# SensorsConnectorBrd.net
KiCad netlist of a schematic drawn in Altium Designer
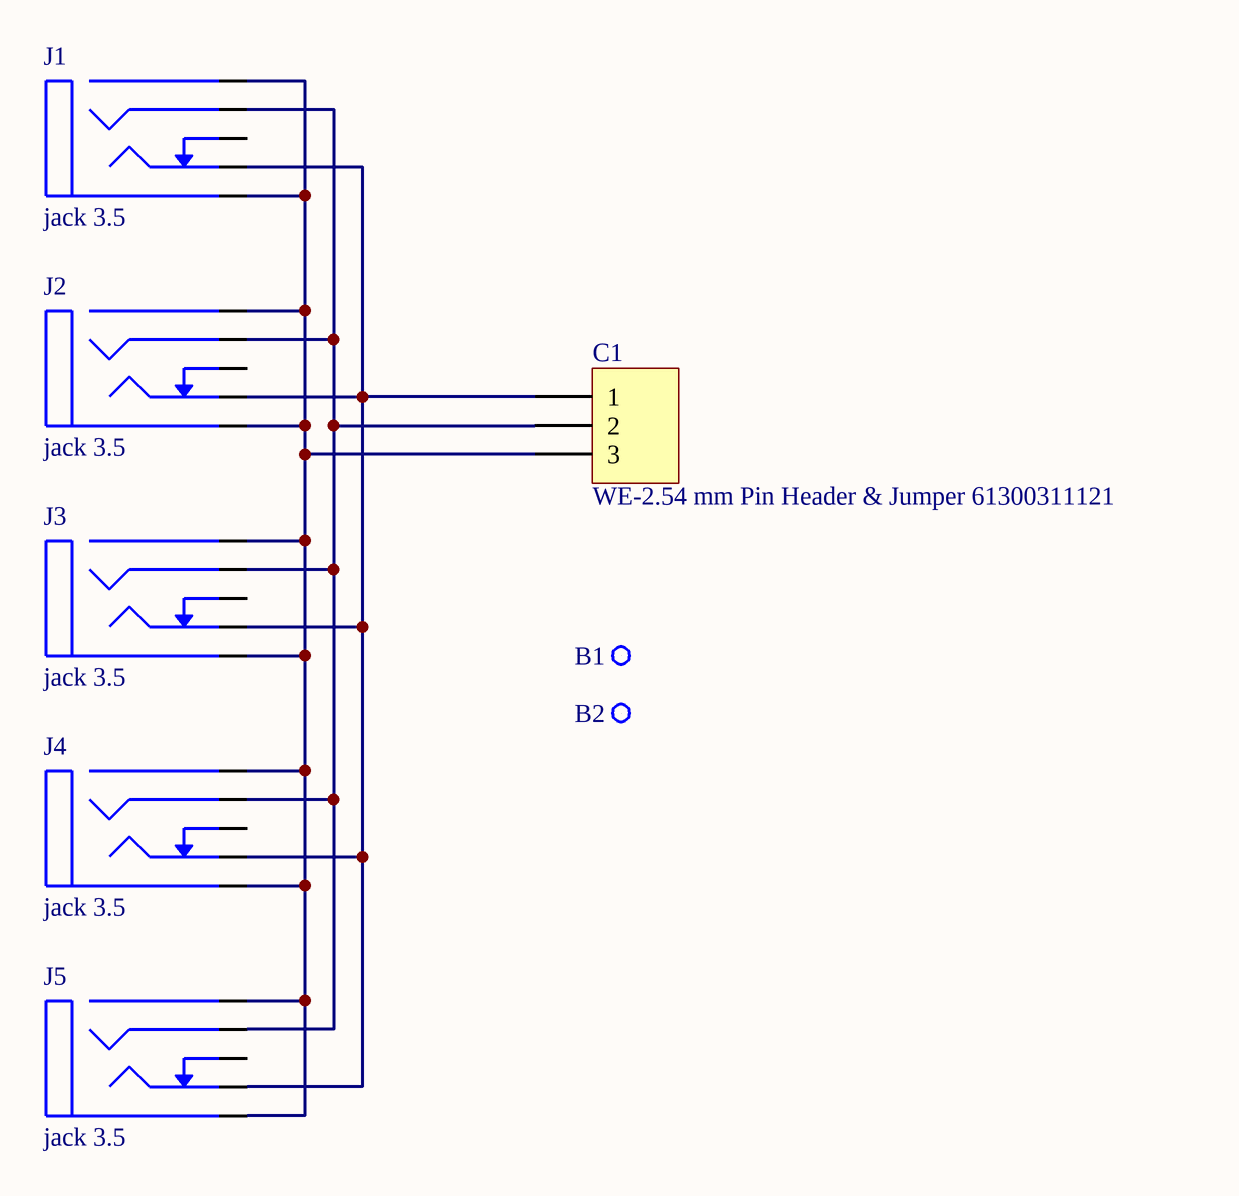
[diagram p0: SensorsConnectorBrd.SchDoc]

(export (version "E")
  (design (tool "Eeschema 10.0.6"))
  (components
    (comp (ref "B1")
      (value "Non Plated Hole")
      (footprint "MTG300")
      (description "Single Terminal Socket")
      (fields (field (name "PART NUMBER") "NON-PLATED_HOLE3.0") (field (name "AUTHOR") "CERN DEM JLC"))
      (libsource (lib "Eletro-mechanical") (part "Single Terminal Socket"))
    )
    (comp (ref "B2")
      (value "Non Plated Hole")
      (footprint "MTG300")
      (description "Single Terminal Socket")
      (fields (field (name "PART NUMBER") "NON-PLATED_HOLE3.0") (field (name "AUTHOR") "CERN DEM JLC"))
      (libsource (lib "Eletro-mechanical") (part "Single Terminal Socket"))
    )
    (comp (ref "C1")
      (value "WE-2.54 mm Pin Header & Jumper 61300311121")
      (footprint "61300311121")
      (description "WR-PHD 2.54mm Pin Header")
      (fields
        (field (name "MANUFACTURER") "WЁ№rth Elektronik eiSos GmbH")
        (field (name "PARTNO") "61300311121")
        (field (name "CREATED BY") "Karrer Zheng")
      )
      (libsource (lib "WE_WR-PHD_Pin Header_2.54mm_rev15c") (part "WE-2.54 mm Pin Header & Jumper 61300311121"))
    )
    (comp (ref "J1")
      (value "jack 3.5")
      (footprint "Jak-Ph St 6x14")
      (libsource (lib "PowerLib") (part "jack 3.5"))
    )
    (comp (ref "J2")
      (value "jack 3.5")
      (footprint "Jak-Ph St 6x14")
      (libsource (lib "PowerLib") (part "jack 3.5"))
    )
    (comp (ref "J3")
      (value "jack 3.5")
      (footprint "Jak-Ph St 6x14")
      (libsource (lib "PowerLib") (part "jack 3.5"))
    )
    (comp (ref "J4")
      (value "jack 3.5")
      (footprint "Jak-Ph St 6x14")
      (libsource (lib "PowerLib") (part "jack 3.5"))
    )
    (comp (ref "J5")
      (value "jack 3.5")
      (footprint "Jak-Ph St 6x14")
      (libsource (lib "PowerLib") (part "jack 3.5"))
    )
  )
  (nets
    (net (code "1") (name "Net-(C1-Pad1)") (class "Default")
      (node (ref "C1") (pin "1") (pinfunction "1_1") (pintype "passive"))
      (node (ref "J1") (pin "4") (pinfunction "4_4") (pintype "passive"))
      (node (ref "J2") (pin "4") (pinfunction "4_4") (pintype "passive"))
      (node (ref "J3") (pin "4") (pinfunction "4_4") (pintype "passive"))
      (node (ref "J4") (pin "4") (pinfunction "4_4") (pintype "passive"))
      (node (ref "J5") (pin "4") (pinfunction "4_4") (pintype "passive"))
    )
    (net (code "2") (name "Net-(C1-Pad2)") (class "Default")
      (node (ref "C1") (pin "2") (pinfunction "2_2") (pintype "passive"))
      (node (ref "J1") (pin "3") (pinfunction "3_3") (pintype "passive"))
      (node (ref "J2") (pin "3") (pinfunction "3_3") (pintype "passive"))
      (node (ref "J3") (pin "3") (pinfunction "3_3") (pintype "passive"))
      (node (ref "J4") (pin "3") (pinfunction "3_3") (pintype "passive"))
      (node (ref "J5") (pin "3") (pinfunction "3_3") (pintype "passive"))
    )
    (net (code "3") (name "Net-(J1-G)") (class "Default")
      (node (ref "C1") (pin "3") (pinfunction "3_3") (pintype "passive"))
      (node (ref "J1") (pin "1") (pinfunction "G1_1") (pintype "passive"))
      (node (ref "J1") (pin "2") (pinfunction "G_2") (pintype "passive"))
      (node (ref "J2") (pin "1") (pinfunction "G1_1") (pintype "passive"))
      (node (ref "J2") (pin "2") (pinfunction "G_2") (pintype "passive"))
      (node (ref "J3") (pin "1") (pinfunction "G1_1") (pintype "passive"))
      (node (ref "J3") (pin "2") (pinfunction "G_2") (pintype "passive"))
      (node (ref "J4") (pin "1") (pinfunction "G1_1") (pintype "passive"))
      (node (ref "J4") (pin "2") (pinfunction "G_2") (pintype "passive"))
      (node (ref "J5") (pin "1") (pinfunction "G1_1") (pintype "passive"))
      (node (ref "J5") (pin "2") (pinfunction "G_2") (pintype "passive"))
    )
    (net (code "4") (name "unconnected-(B1-Pad1)") (class "Default")
      (node (ref "B1") (pin "1") (pinfunction "1_1") (pintype "bidirectional"))
    )
    (net (code "5") (name "unconnected-(B2-Pad1)") (class "Default")
      (node (ref "B2") (pin "1") (pinfunction "1_1") (pintype "bidirectional"))
    )
    (net (code "6") (name "unconnected-(J1-Pad5)") (class "Default")
      (node (ref "J1") (pin "5") (pinfunction "5_5") (pintype "passive"))
    )
    (net (code "7") (name "unconnected-(J2-Pad5)") (class "Default")
      (node (ref "J2") (pin "5") (pinfunction "5_5") (pintype "passive"))
    )
    (net (code "8") (name "unconnected-(J3-Pad5)") (class "Default")
      (node (ref "J3") (pin "5") (pinfunction "5_5") (pintype "passive"))
    )
    (net (code "9") (name "unconnected-(J4-Pad5)") (class "Default")
      (node (ref "J4") (pin "5") (pinfunction "5_5") (pintype "passive"))
    )
    (net (code "10") (name "unconnected-(J5-Pad5)") (class "Default")
      (node (ref "J5") (pin "5") (pinfunction "5_5") (pintype "passive"))
    )
  )
)
